# DoorCard.net
KiCad netlist of a schematic drawn in Altium Designer
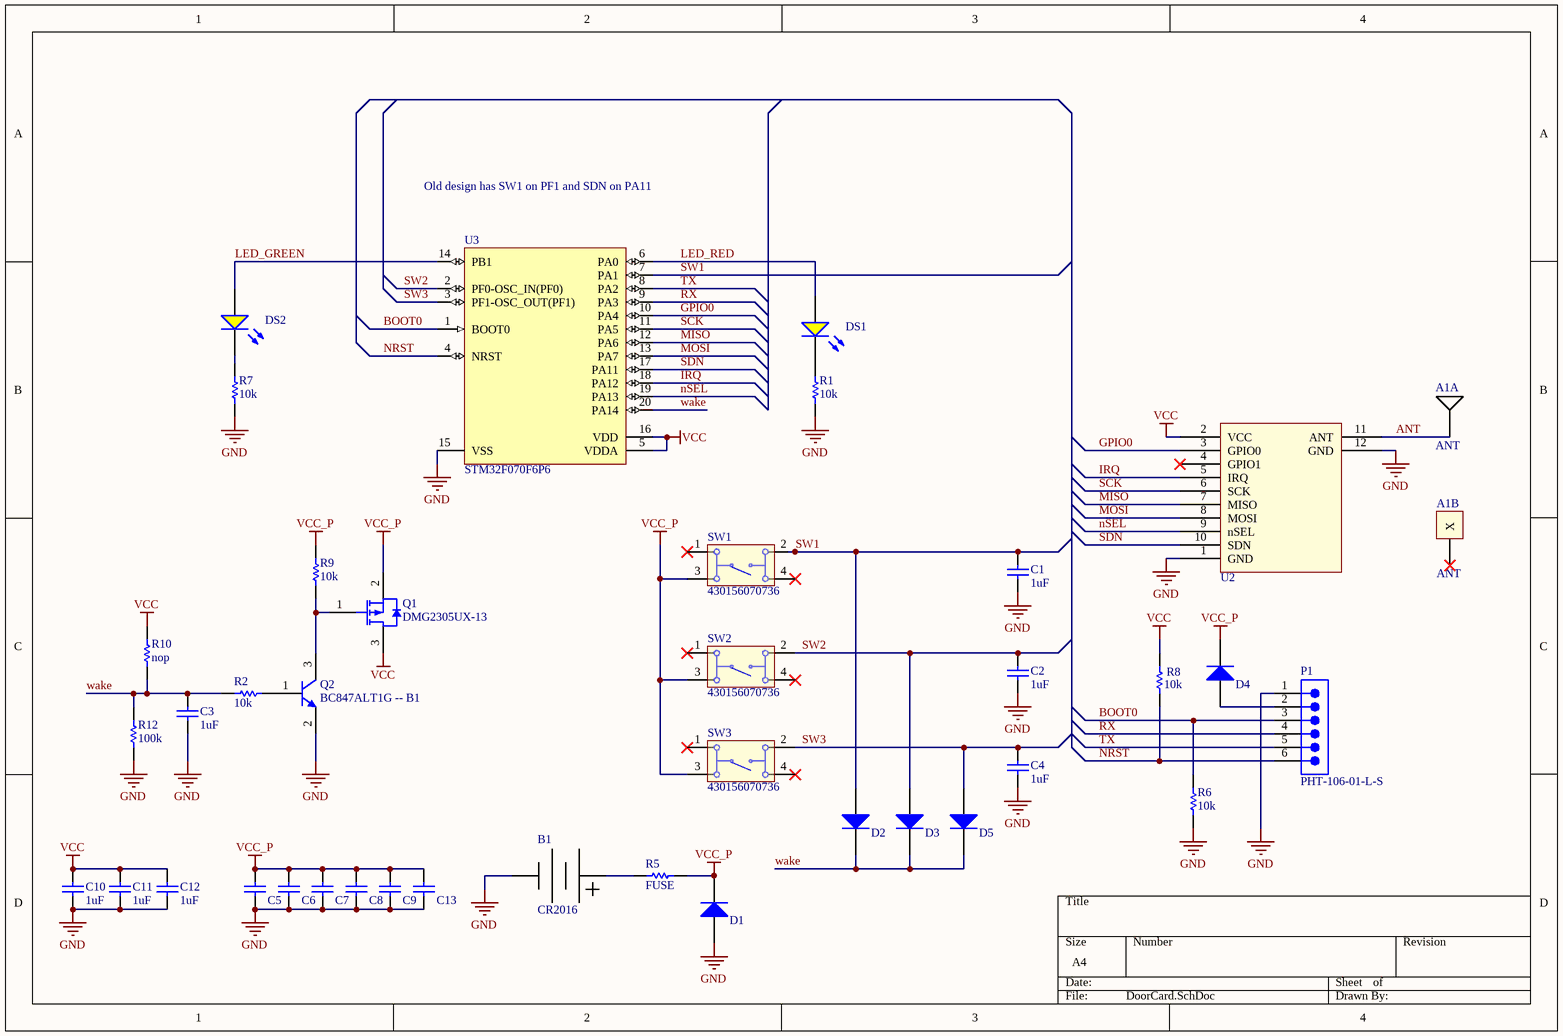
[diagram p0: DoorCard.SchDoc]

(export (version "E")
  (design (tool "Eeschema 10.0.6"))
  (components
    (comp (ref "A1")
      (value "ANT")
      (footprint "433MHz_Antenna")
      (description "ANT1204F002R0433A")
      (libsource (lib "Antenna") (part "ANT1204F002R0433A"))
    )
    (comp (ref "B1")
      (value "CR2016")
      (footprint "CR2012")
      (description "BAT-HLD-002-SMT")
      (libsource (lib "Cell") (part "BAT-HLD-002-SMT"))
    )
    (comp (ref "C1")
      (value "1uF")
      (footprint "CAPC0805(2012)100_M")
      (description "CAP 1uF 25V ±10% 0805 (2012 Metric) Thickness 1mm SMD")
      (fields (field (name "TOLERANCE") "Â±10%"))
      (libsource (lib "Altium Content Vault") (part "CAP"))
    )
    (comp (ref "C2")
      (value "1uF")
      (footprint "CAPC0805(2012)100_M")
      (description "CAP 1uF 25V ±10% 0805 (2012 Metric) Thickness 1mm SMD")
      (fields (field (name "TOLERANCE") "Â±10%"))
      (libsource (lib "Altium Content Vault") (part "CAP"))
    )
    (comp (ref "C3")
      (value "1uF")
      (footprint "CAPC0805(2012)100_M")
      (description "CAP 1uF 25V ±10% 0805 (2012 Metric) Thickness 1mm SMD")
      (fields (field (name "TOLERANCE") "Â±10%"))
      (libsource (lib "Altium Content Vault") (part "CAP"))
    )
    (comp (ref "C4")
      (value "1uF")
      (footprint "CAPC0805(2012)100_M")
      (description "CAP 1uF 25V ±10% 0805 (2012 Metric) Thickness 1mm SMD")
      (fields (field (name "TOLERANCE") "Â±10%"))
      (libsource (lib "Altium Content Vault") (part "CAP"))
    )
    (comp (ref "C5")
      (value "CAP 47uF 6.3V 1206(3216)")
      (footprint "CAPC1206(3216)190_M")
      (description "CAP 47uF 6.3V ±20% 1206 (3216 Metric) Thickness 1.9mm SMD")
      (fields (field (name "TOLERANCE") "Â±20%"))
      (libsource (lib "Altium Content Vault") (part "CMP-1037-05000-1"))
    )
    (comp (ref "C6")
      (value "CAP 47uF 6.3V 1206(3216)")
      (footprint "CAPC1206(3216)190_M")
      (description "CAP 47uF 6.3V ±20% 1206 (3216 Metric) Thickness 1.9mm SMD")
      (fields (field (name "TOLERANCE") "Â±20%"))
      (libsource (lib "Altium Content Vault") (part "CMP-1037-05000-1"))
    )
    (comp (ref "C7")
      (value "CAP 47uF 6.3V 1206(3216)")
      (footprint "CAPC1206(3216)190_M")
      (description "CAP 47uF 6.3V ±20% 1206 (3216 Metric) Thickness 1.9mm SMD")
      (fields (field (name "TOLERANCE") "Â±20%"))
      (libsource (lib "Altium Content Vault") (part "CMP-1037-05000-1"))
    )
    (comp (ref "C8")
      (value "CAP 47uF 6.3V 1206(3216)")
      (footprint "CAPC1206(3216)190_M")
      (description "CAP 47uF 6.3V ±20% 1206 (3216 Metric) Thickness 1.9mm SMD")
      (fields (field (name "TOLERANCE") "Â±20%"))
      (libsource (lib "Altium Content Vault") (part "CMP-1037-05000-1"))
    )
    (comp (ref "C9")
      (value "CAP 47uF 6.3V 1206(3216)")
      (footprint "CAPC1206(3216)190_M")
      (description "CAP 47uF 6.3V ±20% 1206 (3216 Metric) Thickness 1.9mm SMD")
      (fields (field (name "TOLERANCE") "Â±20%"))
      (libsource (lib "Altium Content Vault") (part "CMP-1037-05000-1"))
    )
    (comp (ref "C10")
      (value "1uF")
      (footprint "CAPC0805(2012)100_M")
      (description "CAP 1uF 25V ±10% 0805 (2012 Metric) Thickness 1mm SMD")
      (fields (field (name "TOLERANCE") "Â±10%"))
      (libsource (lib "Altium Content Vault") (part "CAP"))
    )
    (comp (ref "C11")
      (value "1uF")
      (footprint "CAPC0805(2012)100_M")
      (description "CAP 1uF 25V ±10% 0805 (2012 Metric) Thickness 1mm SMD")
      (fields (field (name "TOLERANCE") "Â±10%"))
      (libsource (lib "Altium Content Vault") (part "CAP"))
    )
    (comp (ref "C12")
      (value "1uF")
      (footprint "CAPC0805(2012)100_M")
      (description "CAP 1uF 25V ±10% 0805 (2012 Metric) Thickness 1mm SMD")
      (fields (field (name "TOLERANCE") "Â±10%"))
      (libsource (lib "Altium Content Vault") (part "CAP"))
    )
    (comp (ref "C13")
      (value "CAP 47uF 6.3V 1206(3216)")
      (footprint "CAPC1206(3216)190_M")
      (description "CAP 47uF 6.3V ±20% 1206 (3216 Metric) Thickness 1.9mm SMD")
      (fields (field (name "TOLERANCE") "Â±20%"))
      (libsource (lib "Altium Content Vault") (part "CMP-1037-05000-1"))
    )
    (comp (ref "D1")
      (value "MMSD4148T3G")
      (footprint "ONSC-SOD123-2-425G-04_V")
      (description "Switching Diode, 100 V, 200 mA, -55 to 150 degC, 2-Pin SOD123 (425), RoHS, Tape and Reel")
      (fields (field (name "MANUFACTURER") "ON Semiconductor"))
      (libsource (lib "Altium Content Vault") (part "ONSC-MMSD4148-SOD123-2"))
    )
    (comp (ref "D2")
      (value "MMSD4148T3G")
      (footprint "ONSC-SOD123-2-425G-04_V")
      (description "Switching Diode, 100 V, 200 mA, -55 to 150 degC, 2-Pin SOD123 (425), RoHS, Tape and Reel")
      (fields (field (name "MANUFACTURER") "ON Semiconductor"))
      (libsource (lib "Altium Content Vault") (part "ONSC-MMSD4148-SOD123-2"))
    )
    (comp (ref "D3")
      (value "MMSD4148T3G")
      (footprint "ONSC-SOD123-2-425G-04_V")
      (description "Switching Diode, 100 V, 200 mA, -55 to 150 degC, 2-Pin SOD123 (425), RoHS, Tape and Reel")
      (fields (field (name "MANUFACTURER") "ON Semiconductor"))
      (libsource (lib "Altium Content Vault") (part "ONSC-MMSD4148-SOD123-2"))
    )
    (comp (ref "D4")
      (value "MMSD4148T3G")
      (footprint "ONSC-SOD123-2-425G-04_V")
      (description "Switching Diode, 100 V, 200 mA, -55 to 150 degC, 2-Pin SOD123 (425), RoHS, Tape and Reel")
      (fields (field (name "MANUFACTURER") "ON Semiconductor"))
      (libsource (lib "Altium Content Vault") (part "ONSC-MMSD4148-SOD123-2"))
    )
    (comp (ref "D5")
      (value "MMSD4148T3G")
      (footprint "ONSC-SOD123-2-425G-04_V")
      (description "Switching Diode, 100 V, 200 mA, -55 to 150 degC, 2-Pin SOD123 (425), RoHS, Tape and Reel")
      (fields (field (name "MANUFACTURER") "ON Semiconductor"))
      (libsource (lib "Altium Content Vault") (part "ONSC-MMSD4148-SOD123-2"))
    )
    (comp (ref "DS1")
      (value "LTST-C170YKT")
      (footprint "LTST-C170YKT_V")
      (description "LED YELLOW CLEAR 0805 SMD")
      (libsource (lib "Altium Content Vault") (part "LED_YELLOW_AC"))
    )
    (comp (ref "DS2")
      (value "LTST-C170YKT")
      (footprint "LTST-C170YKT_V")
      (description "LED YELLOW CLEAR 0805 SMD")
      (libsource (lib "Altium Content Vault") (part "LED_YELLOW_AC"))
    )
    (comp (ref "P1")
      (value "PHT-106-01-L-S")
      (footprint "SMTC-PHT-106-01-X-S")
      (description "Press Fit Header, Through-hole, Vertical, -55 to 125 degC, 2.54 mm Pitch, 6-Pin, Male, RoHS")
      (fields (field (name "MANUFACTURER") "Samtec"))
      (libsource (lib "Altium Content Vault") (part "SMTC-PHT-106-01-X-S"))
    )
    (comp (ref "Q1")
      (value "DMG2305UX-13")
      (footprint "FAIR-SOT23-3_V")
      (fields (field (name "TOLERANCE") "30ppm"))
      (libsource (lib "Altium Content Vault") (part "PEMOS-GSD-3"))
    )
    (comp (ref "Q2")
      (value "BC847ALT1G -- B1")
      (footprint "ONSC-SOT-23-3-318-08_V")
      (description "General Purpose Transistor, NPN Silicon, 3-Pin SOT-23, Pb-Free, Tape and Reel")
      (fields (field (name "PARTNUMBER") "BC847ALT1G") (field (name "MANUFACTURER") "On Semiconductor"))
      (libsource (lib "Altium Content Vault") (part "ONSC-NPN-B1E2C3-3"))
    )
    (comp (ref "R1")
      (value "10k")
      (footprint "RESC0805(2012)_L")
      (description "10K2 0.125W 1% 0805 (2012 Metric)  SMD")
      (fields (field (name "TOLERANCE") "1 %") (field (name "POWER") "0.125 W"))
      (libsource (lib "Altium Content Vault") (part "RES"))
    )
    (comp (ref "R2")
      (value "10k")
      (footprint "RESC0805(2012)_L")
      (fields (field (name "TOLERANCE") "1 %") (field (name "POWER") "0.125 W"))
      (libsource (lib "Altium Content Vault") (part "RES"))
    )
    (comp (ref "R5")
      (value "FUSE")
      (footprint "RESC0805(2012)_L")
      (description "PTC Fuse")
      (fields (field (name "TOLERANCE") "1 %") (field (name "POWER") "0.125 W"))
      (libsource (lib "Altium Content Vault") (part "RES"))
    )
    (comp (ref "R6")
      (value "10k")
      (footprint "RESC0805(2012)_L")
      (description "10K2 0.125W 1% 0805 (2012 Metric)  SMD")
      (fields (field (name "TOLERANCE") "1 %") (field (name "POWER") "0.125 W"))
      (libsource (lib "Altium Content Vault") (part "RES"))
    )
    (comp (ref "R7")
      (value "10k")
      (footprint "RESC0805(2012)_L")
      (description "10K2 0.125W 1% 0805 (2012 Metric)  SMD")
      (fields (field (name "TOLERANCE") "1 %") (field (name "POWER") "0.125 W"))
      (libsource (lib "Altium Content Vault") (part "RES"))
    )
    (comp (ref "R8")
      (value "10k")
      (footprint "RESC0805(2012)_L")
      (description "10K2 0.125W 1% 0805 (2012 Metric)  SMD")
      (fields (field (name "TOLERANCE") "1 %") (field (name "POWER") "0.125 W"))
      (libsource (lib "Altium Content Vault") (part "RES"))
    )
    (comp (ref "R9")
      (value "10k")
      (footprint "RESC0805(2012)_L")
      (description "10K2 0.125W 1% 0805 (2012 Metric)  SMD")
      (fields (field (name "TOLERANCE") "1 %") (field (name "POWER") "0.125 W"))
      (libsource (lib "Altium Content Vault") (part "RES"))
    )
    (comp (ref "R10")
      (value "nop")
      (footprint "RESC0805(2012)_L")
      (fields (field (name "TOLERANCE") "1 %") (field (name "POWER") "0.125 W"))
      (libsource (lib "Altium Content Vault") (part "RES"))
    )
    (comp (ref "R12")
      (value "100k")
      (footprint "RESC0805(2012)_L")
      (fields (field (name "TOLERANCE") "1 %") (field (name "POWER") "0.125 W"))
      (libsource (lib "Altium Content Vault") (part "RES"))
    )
    (comp (ref "SW1")
      (value "430156070736")
      (footprint "430156070736")
      (description "WS-TATV THT Tact Switch 6X6 mm")
      (fields (field (name "MANUFACTURER") "Wuerth Elektronik"))
      (libsource (lib "Altium Content Vault") (part "WE-TACT-SW-4"))
    )
    (comp (ref "SW2")
      (value "430156070736")
      (footprint "430156070736")
      (description "WS-TATV THT Tact Switch 6X6 mm")
      (fields (field (name "MANUFACTURER") "Wuerth Elektronik"))
      (libsource (lib "Altium Content Vault") (part "WE-TACT-SW-4"))
    )
    (comp (ref "SW3")
      (value "430156070736")
      (footprint "430156070736")
      (description "WS-TATV THT Tact Switch 6X6 mm")
      (fields (field (name "MANUFACTURER") "Wuerth Elektronik"))
      (libsource (lib "Altium Content Vault") (part "WE-TACT-SW-4"))
    )
    (comp (ref "U2")
      (value "Si4463")
      (footprint "E10-433MS")
      (description "E10-433MS")
      (libsource (lib "SiliconLabs") (part "Component_1"))
    )
    (comp (ref "U3")
      (value "STM32F070F6P6")
      (footprint "STM-TSSOP20_M")
      (fields (field (name "MANUFACTURER") "STMicroelectronics"))
      (libsource (lib "Altium Content Vault") (part "MC-ARM-STM32F070-TSSOP20"))
    )
  )
  (nets
    (net (code "1") (name "/ANT") (class "Default")
      (node (ref "A1") (pin "1") (pinfunction "ANT_1") (pintype "passive"))
      (node (ref "U2") (pin "11") (pinfunction "ANT_11") (pintype "passive"))
    )
    (net (code "2") (name "/BOOT0") (class "Default")
      (node (ref "P1") (pin "3") (pinfunction "3_3") (pintype "passive"))
      (node (ref "R6") (pin "2") (pinfunction "2_2") (pintype "passive"))
      (node (ref "U3") (pin "1") (pinfunction "BOOT0_1") (pintype "input"))
    )
    (net (code "3") (name "/GPIO0") (class "Default")
      (node (ref "U2") (pin "3") (pinfunction "GPIO0_3") (pintype "passive"))
      (node (ref "U3") (pin "10") (pinfunction "PA4_10") (pintype "bidirectional"))
    )
    (net (code "4") (name "/IRQ") (class "Default")
      (node (ref "U2") (pin "5") (pinfunction "IRQ_5") (pintype "passive"))
      (node (ref "U3") (pin "18") (pinfunction "PA12_18") (pintype "bidirectional"))
    )
    (net (code "5") (name "/LED_GREEN") (class "Default")
      (node (ref "DS2") (pin "A") (pinfunction "A_A") (pintype "passive"))
      (node (ref "U3") (pin "14") (pinfunction "PB1_14") (pintype "bidirectional"))
    )
    (net (code "6") (name "/LED_RED") (class "Default")
      (node (ref "DS1") (pin "A") (pinfunction "A_A") (pintype "passive"))
      (node (ref "U3") (pin "6") (pinfunction "PA0_6") (pintype "bidirectional"))
    )
    (net (code "7") (name "/MISO") (class "Default")
      (node (ref "U2") (pin "7") (pinfunction "MISO_7") (pintype "passive"))
      (node (ref "U3") (pin "12") (pinfunction "PA6_12") (pintype "bidirectional"))
    )
    (net (code "8") (name "/MOSI") (class "Default")
      (node (ref "U2") (pin "8") (pinfunction "MOSI_8") (pintype "passive"))
      (node (ref "U3") (pin "13") (pinfunction "PA7_13") (pintype "bidirectional"))
    )
    (net (code "9") (name "/NRST") (class "Default")
      (node (ref "P1") (pin "6") (pinfunction "6_6") (pintype "passive"))
      (node (ref "R8") (pin "1") (pinfunction "1_1") (pintype "passive"))
      (node (ref "U3") (pin "4") (pinfunction "NRST_4") (pintype "bidirectional"))
    )
    (net (code "10") (name "/RX") (class "Default")
      (node (ref "P1") (pin "4") (pinfunction "4_4") (pintype "passive"))
      (node (ref "U3") (pin "9") (pinfunction "PA3_9") (pintype "bidirectional"))
    )
    (net (code "11") (name "/SCK") (class "Default")
      (node (ref "U2") (pin "6") (pinfunction "SCK_6") (pintype "passive"))
      (node (ref "U3") (pin "11") (pinfunction "PA5_11") (pintype "bidirectional"))
    )
    (net (code "12") (name "/SDN") (class "Default")
      (node (ref "U2") (pin "10") (pinfunction "SDN_10") (pintype "passive"))
      (node (ref "U3") (pin "17") (pinfunction "PA11_17") (pintype "bidirectional"))
    )
    (net (code "13") (name "/SW1") (class "Default")
      (node (ref "C1") (pin "2") (pinfunction "2_2") (pintype "passive"))
      (node (ref "D2") (pin "2") (pinfunction "ANODE_2") (pintype "passive"))
      (node (ref "SW1") (pin "2") (pinfunction "2_2") (pintype "passive"))
      (node (ref "U3") (pin "7") (pinfunction "PA1_7") (pintype "bidirectional"))
    )
    (net (code "14") (name "/SW2") (class "Default")
      (node (ref "C2") (pin "2") (pinfunction "2_2") (pintype "passive"))
      (node (ref "D3") (pin "2") (pinfunction "ANODE_2") (pintype "passive"))
      (node (ref "SW2") (pin "2") (pinfunction "2_2") (pintype "passive"))
      (node (ref "U3") (pin "2") (pinfunction "PF0-OSC_IN(PF0)_2") (pintype "bidirectional"))
    )
    (net (code "15") (name "/SW3") (class "Default")
      (node (ref "C4") (pin "2") (pinfunction "2_2") (pintype "passive"))
      (node (ref "D5") (pin "2") (pinfunction "ANODE_2") (pintype "passive"))
      (node (ref "SW3") (pin "2") (pinfunction "2_2") (pintype "passive"))
      (node (ref "U3") (pin "3") (pinfunction "PF1-OSC_OUT(PF1)_3") (pintype "bidirectional"))
    )
    (net (code "16") (name "/TX") (class "Default")
      (node (ref "P1") (pin "5") (pinfunction "5_5") (pintype "passive"))
      (node (ref "U3") (pin "8") (pinfunction "PA2_8") (pintype "bidirectional"))
    )
    (net (code "17") (name "/nSEL") (class "Default")
      (node (ref "U2") (pin "9") (pinfunction "nSEL_9") (pintype "passive"))
      (node (ref "U3") (pin "19") (pinfunction "PA13_19") (pintype "bidirectional"))
    )
    (net (code "18") (name "/wake") (class "Default")
      (node (ref "C3") (pin "2") (pinfunction "2_2") (pintype "passive"))
      (node (ref "D2") (pin "1") (pinfunction "CATHODE_1") (pintype "passive"))
      (node (ref "D3") (pin "1") (pinfunction "CATHODE_1") (pintype "passive"))
      (node (ref "D5") (pin "1") (pinfunction "CATHODE_1") (pintype "passive"))
      (node (ref "R10") (pin "1") (pinfunction "1_1") (pintype "passive"))
      (node (ref "R12") (pin "2") (pinfunction "2_2") (pintype "passive"))
      (node (ref "R2") (pin "2") (pinfunction "2_2") (pintype "passive"))
      (node (ref "U3") (pin "20") (pinfunction "PA14_20") (pintype "bidirectional"))
    )
    (net (code "19") (name "GND") (class "Default")
      (node (ref "B1") (pin "2") (pinfunction "2_2") (pintype "passive"))
      (node (ref "C1") (pin "1") (pinfunction "1_1") (pintype "passive"))
      (node (ref "C10") (pin "1") (pinfunction "1_1") (pintype "passive"))
      (node (ref "C11") (pin "1") (pinfunction "1_1") (pintype "passive"))
      (node (ref "C12") (pin "1") (pinfunction "1_1") (pintype "passive"))
      (node (ref "C13") (pin "1") (pinfunction "1_1") (pintype "passive"))
      (node (ref "C2") (pin "1") (pinfunction "1_1") (pintype "passive"))
      (node (ref "C3") (pin "1") (pinfunction "1_1") (pintype "passive"))
      (node (ref "C4") (pin "1") (pinfunction "1_1") (pintype "passive"))
      (node (ref "C5") (pin "1") (pinfunction "1_1") (pintype "passive"))
      (node (ref "C6") (pin "1") (pinfunction "1_1") (pintype "passive"))
      (node (ref "C7") (pin "1") (pinfunction "1_1") (pintype "passive"))
      (node (ref "C8") (pin "1") (pinfunction "1_1") (pintype "passive"))
      (node (ref "C9") (pin "1") (pinfunction "1_1") (pintype "passive"))
      (node (ref "D1") (pin "2") (pinfunction "ANODE_2") (pintype "passive"))
      (node (ref "P1") (pin "1") (pinfunction "1_1") (pintype "passive"))
      (node (ref "Q2") (pin "2") (pinfunction "E_2") (pintype "passive"))
      (node (ref "R1") (pin "1") (pinfunction "1_1") (pintype "passive"))
      (node (ref "R12") (pin "1") (pinfunction "1_1") (pintype "passive"))
      (node (ref "R6") (pin "1") (pinfunction "1_1") (pintype "passive"))
      (node (ref "R7") (pin "1") (pinfunction "1_1") (pintype "passive"))
      (node (ref "U2") (pin "1") (pinfunction "GND_1") (pintype "passive"))
      (node (ref "U2") (pin "12") (pinfunction "GND_12") (pintype "passive"))
      (node (ref "U3") (pin "15") (pinfunction "VSS_15") (pintype "power_in"))
    )
    (net (code "20") (name "Net-(B1-Pad1)") (class "Default")
      (node (ref "B1") (pin "1") (pinfunction "1_1") (pintype "passive"))
      (node (ref "R5") (pin "2") (pinfunction "2_2") (pintype "passive"))
    )
    (net (code "21") (name "Net-(D4-ANODE)") (class "Default")
      (node (ref "D4") (pin "2") (pinfunction "ANODE_2") (pintype "passive"))
      (node (ref "P1") (pin "2") (pinfunction "2_2") (pintype "passive"))
    )
    (net (code "22") (name "Net-(DS1-PadC)") (class "Default")
      (node (ref "DS1") (pin "C") (pinfunction "C_C") (pintype "passive"))
      (node (ref "R1") (pin "2") (pinfunction "2_2") (pintype "passive"))
    )
    (net (code "23") (name "Net-(DS2-PadC)") (class "Default")
      (node (ref "DS2") (pin "C") (pinfunction "C_C") (pintype "passive"))
      (node (ref "R7") (pin "2") (pinfunction "2_2") (pintype "passive"))
    )
    (net (code "24") (name "Net-(Q1-GATE)") (class "Default")
      (node (ref "Q1") (pin "1") (pinfunction "GATE_1") (pintype "passive"))
      (node (ref "Q2") (pin "3") (pinfunction "C_3") (pintype "passive"))
      (node (ref "R9") (pin "1") (pinfunction "1_1") (pintype "passive"))
    )
    (net (code "25") (name "Net-(Q2-B)") (class "Default")
      (node (ref "Q2") (pin "1") (pinfunction "B_1") (pintype "passive"))
      (node (ref "R2") (pin "1") (pinfunction "1_1") (pintype "passive"))
    )
    (net (code "26") (name "VCC") (class "Default")
      (node (ref "C10") (pin "2") (pinfunction "2_2") (pintype "passive"))
      (node (ref "C11") (pin "2") (pinfunction "2_2") (pintype "passive"))
      (node (ref "C12") (pin "2") (pinfunction "2_2") (pintype "passive"))
      (node (ref "Q1") (pin "3") (pinfunction "DRAIN_3") (pintype "passive"))
      (node (ref "R10") (pin "2") (pinfunction "2_2") (pintype "passive"))
      (node (ref "R8") (pin "2") (pinfunction "2_2") (pintype "passive"))
      (node (ref "U2") (pin "2") (pinfunction "VCC_2") (pintype "passive"))
      (node (ref "U3") (pin "16") (pinfunction "VDD_16") (pintype "power_in"))
      (node (ref "U3") (pin "5") (pinfunction "VDDA_5") (pintype "power_in"))
    )
    (net (code "27") (name "VCC_P") (class "Default")
      (node (ref "C13") (pin "2") (pinfunction "2_2") (pintype "passive"))
      (node (ref "C5") (pin "2") (pinfunction "2_2") (pintype "passive"))
      (node (ref "C6") (pin "2") (pinfunction "2_2") (pintype "passive"))
      (node (ref "C7") (pin "2") (pinfunction "2_2") (pintype "passive"))
      (node (ref "C8") (pin "2") (pinfunction "2_2") (pintype "passive"))
      (node (ref "C9") (pin "2") (pinfunction "2_2") (pintype "passive"))
      (node (ref "D1") (pin "1") (pinfunction "CATHODE_1") (pintype "passive"))
      (node (ref "D4") (pin "1") (pinfunction "CATHODE_1") (pintype "passive"))
      (node (ref "Q1") (pin "2") (pinfunction "SOURCE_2") (pintype "passive"))
      (node (ref "R5") (pin "1") (pinfunction "1_1") (pintype "passive"))
      (node (ref "R9") (pin "2") (pinfunction "2_2") (pintype "passive"))
      (node (ref "SW1") (pin "3") (pinfunction "3_3") (pintype "passive"))
      (node (ref "SW2") (pin "3") (pinfunction "3_3") (pintype "passive"))
      (node (ref "SW3") (pin "3") (pinfunction "3_3") (pintype "passive"))
    )
    (net (code "28") (name "unconnected-(A1B-X-Pad2)") (class "Default")
      (node (ref "A1") (pin "2") (pinfunction "X_2") (pintype "passive+no_connect"))
    )
    (net (code "29") (name "unconnected-(SW1-Pad1)") (class "Default")
      (node (ref "SW1") (pin "1") (pinfunction "1_1") (pintype "passive+no_connect"))
    )
    (net (code "30") (name "unconnected-(SW1-Pad4)") (class "Default")
      (node (ref "SW1") (pin "4") (pinfunction "4_4") (pintype "passive+no_connect"))
    )
    (net (code "31") (name "unconnected-(SW2-Pad1)") (class "Default")
      (node (ref "SW2") (pin "1") (pinfunction "1_1") (pintype "passive+no_connect"))
    )
    (net (code "32") (name "unconnected-(SW2-Pad4)") (class "Default")
      (node (ref "SW2") (pin "4") (pinfunction "4_4") (pintype "passive+no_connect"))
    )
    (net (code "33") (name "unconnected-(SW3-Pad1)") (class "Default")
      (node (ref "SW3") (pin "1") (pinfunction "1_1") (pintype "passive+no_connect"))
    )
    (net (code "34") (name "unconnected-(SW3-Pad4)") (class "Default")
      (node (ref "SW3") (pin "4") (pinfunction "4_4") (pintype "passive+no_connect"))
    )
    (net (code "35") (name "unconnected-(U2-GPIO1-Pad4)") (class "Default")
      (node (ref "U2") (pin "4") (pinfunction "GPIO1_4") (pintype "passive+no_connect"))
    )
  )
)
